# thermometer.net
KiCad netlist of a schematic drawn in EAGLE
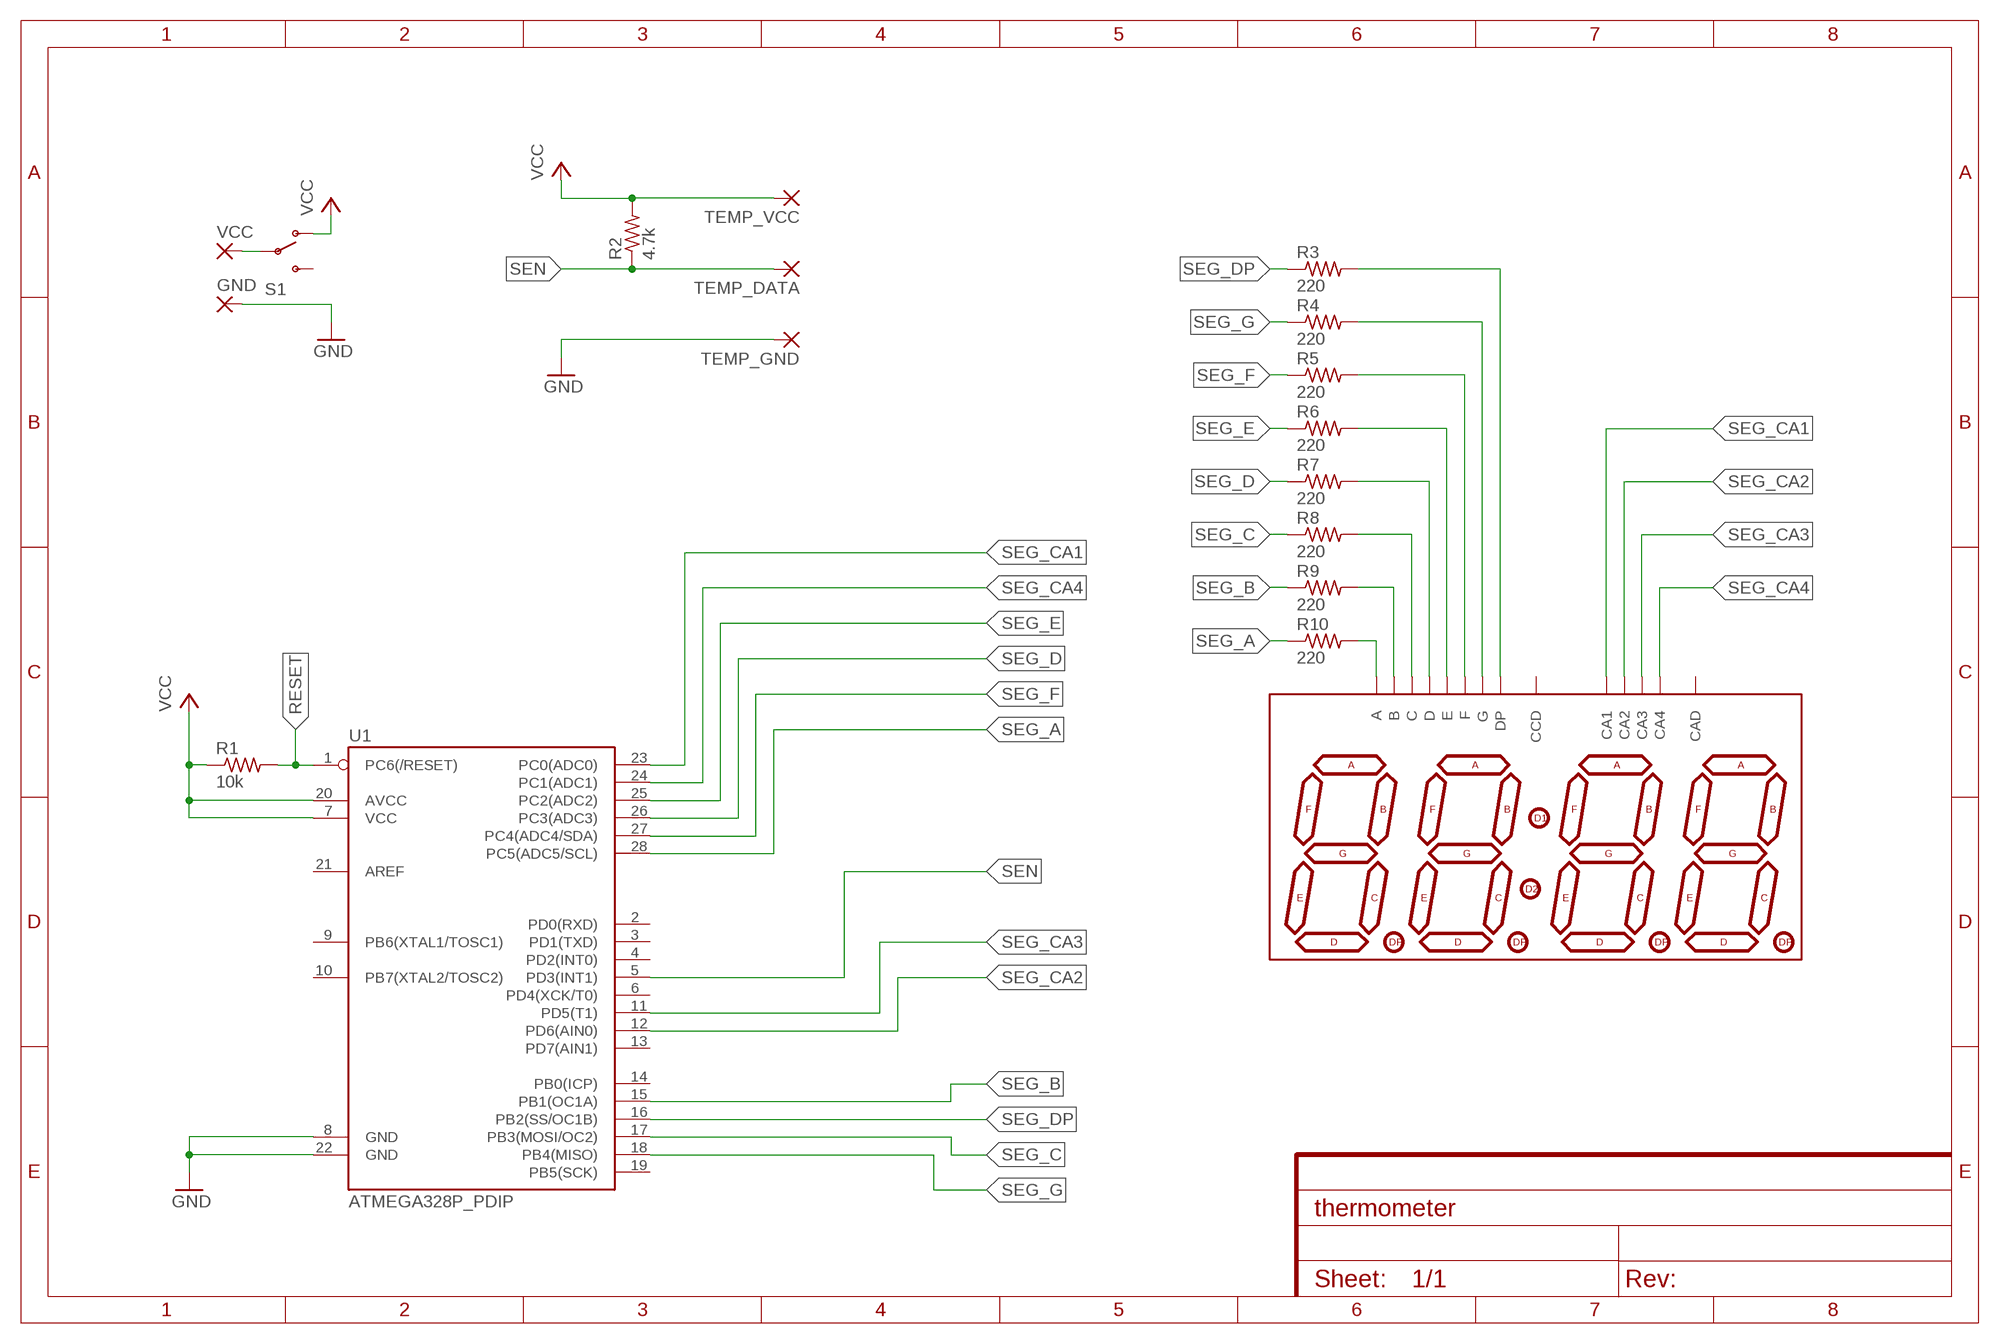
[diagram p0: schematic, sheet 1]

(export (version "E")
  (design (tool "Eeschema 10.0.6"))
  (components
    (comp (ref "GND")
      (value "2,54/0,8")
      (footprint "eagle-import:2,54_0,8")
      (libsource (lib "eagle-import") (part "2,54/0,8"))
    )
    (comp (ref "R1")
      (value "10k")
      (footprint "eagle-import:R0805")
      (libsource (lib "eagle-import") (part "R-US_R0805"))
    )
    (comp (ref "R2")
      (value "4.7k")
      (footprint "eagle-import:R0805")
      (libsource (lib "eagle-import") (part "R-US_R0805"))
    )
    (comp (ref "R3")
      (value "220")
      (footprint "eagle-import:R0805")
      (libsource (lib "eagle-import") (part "R-US_R0805"))
    )
    (comp (ref "R4")
      (value "220")
      (footprint "eagle-import:R0805")
      (libsource (lib "eagle-import") (part "R-US_R0805"))
    )
    (comp (ref "R5")
      (value "220")
      (footprint "eagle-import:R0805")
      (libsource (lib "eagle-import") (part "R-US_R0805"))
    )
    (comp (ref "R6")
      (value "220")
      (footprint "eagle-import:R0805")
      (libsource (lib "eagle-import") (part "R-US_R0805"))
    )
    (comp (ref "R7")
      (value "220")
      (footprint "eagle-import:R0805")
      (libsource (lib "eagle-import") (part "R-US_R0805"))
    )
    (comp (ref "R8")
      (value "220")
      (footprint "eagle-import:R0805")
      (libsource (lib "eagle-import") (part "R-US_R0805"))
    )
    (comp (ref "R9")
      (value "220")
      (footprint "eagle-import:R0805")
      (libsource (lib "eagle-import") (part "R-US_R0805"))
    )
    (comp (ref "R10")
      (value "220")
      (footprint "eagle-import:R0805")
      (libsource (lib "eagle-import") (part "R-US_R0805"))
    )
    (comp (ref "S1")
      (value "SWITCH-SPDTPTH")
      (footprint "eagle-import:SWITCH-SPDT")
      (libsource (lib "eagle-import") (part "SWITCH-SPDTPTH"))
    )
    (comp (ref "TEMP_DATA")
      (value "2,54/0,8")
      (footprint "eagle-import:2,54_0,8")
      (libsource (lib "eagle-import") (part "2,54/0,8"))
    )
    (comp (ref "TEMP_GND")
      (value "2,54/0,8")
      (footprint "eagle-import:2,54_0,8")
      (libsource (lib "eagle-import") (part "2,54/0,8"))
    )
    (comp (ref "TEMP_VCC")
      (value "2,54/0,8")
      (footprint "eagle-import:2,54_0,8")
      (libsource (lib "eagle-import") (part "2,54/0,8"))
    )
    (comp (ref "U1")
      (value "ATMEGA328P_PDIP")
      (footprint "eagle-import:DIL28-3")
      (libsource (lib "eagle-import") (part "ATMEGA328P_PDIP"))
    )
    (comp (ref "U2")
      (value "5461BSDIP14")
      (footprint "eagle-import:5461BS")
      (libsource (lib "eagle-import") (part "5461BSDIP14"))
    )
    (comp (ref "VCC")
      (value "2,54/0,8")
      (footprint "eagle-import:2,54_0,8")
      (libsource (lib "eagle-import") (part "2,54/0,8"))
    )
  )
  (nets
    (net (code "1") (name "GND") (class "Default")
      (node (ref "GND") (pin "1") (pinfunction "P_1") (pintype "passive"))
      (node (ref "TEMP_GND") (pin "1") (pinfunction "P_1") (pintype "passive"))
      (node (ref "U1") (pin "22") (pinfunction "GND_22") (pintype "bidirectional"))
      (node (ref "U1") (pin "8") (pinfunction "GND_8") (pintype "bidirectional"))
    )
    (net (code "2") (name "Net-(R3-Pad2)") (class "Default")
      (node (ref "R3") (pin "2") (pinfunction "2_2") (pintype "passive"))
      (node (ref "U2") (pin "DP") (pinfunction "DP_DP") (pintype "bidirectional"))
    )
    (net (code "3") (name "Net-(R4-Pad2)") (class "Default")
      (node (ref "R4") (pin "2") (pinfunction "2_2") (pintype "passive"))
      (node (ref "U2") (pin "G") (pinfunction "G_G") (pintype "bidirectional"))
    )
    (net (code "4") (name "Net-(R5-Pad2)") (class "Default")
      (node (ref "R5") (pin "2") (pinfunction "2_2") (pintype "passive"))
      (node (ref "U2") (pin "F") (pinfunction "F_F") (pintype "bidirectional"))
    )
    (net (code "5") (name "Net-(R6-Pad2)") (class "Default")
      (node (ref "R6") (pin "2") (pinfunction "2_2") (pintype "passive"))
      (node (ref "U2") (pin "E") (pinfunction "E_E") (pintype "bidirectional"))
    )
    (net (code "6") (name "Net-(R7-Pad2)") (class "Default")
      (node (ref "R7") (pin "2") (pinfunction "2_2") (pintype "passive"))
      (node (ref "U2") (pin "D") (pinfunction "D_D") (pintype "bidirectional"))
    )
    (net (code "7") (name "Net-(R8-Pad2)") (class "Default")
      (node (ref "R8") (pin "2") (pinfunction "2_2") (pintype "passive"))
      (node (ref "U2") (pin "C") (pinfunction "C_C") (pintype "bidirectional"))
    )
    (net (code "8") (name "Net-(R9-Pad2)") (class "Default")
      (node (ref "R9") (pin "2") (pinfunction "2_2") (pintype "passive"))
      (node (ref "U2") (pin "B") (pinfunction "B_B") (pintype "bidirectional"))
    )
    (net (code "9") (name "Net-(R10-Pad2)") (class "Default")
      (node (ref "R10") (pin "2") (pinfunction "2_2") (pintype "passive"))
      (node (ref "U2") (pin "A") (pinfunction "A_A") (pintype "bidirectional"))
    )
    (net (code "10") (name "Net-(S1-P)") (class "Default")
      (node (ref "S1") (pin "2") (pinfunction "P_2") (pintype "passive"))
      (node (ref "VCC") (pin "1") (pinfunction "P_1") (pintype "passive"))
    )
    (net (code "11") (name "RESET") (class "Default")
      (node (ref "R1") (pin "2") (pinfunction "2_2") (pintype "passive"))
      (node (ref "U1") (pin "1") (pinfunction "PC6(/RESET)_1") (pintype "bidirectional"))
    )
    (net (code "12") (name "SEG_A") (class "Default")
      (node (ref "R10") (pin "1") (pinfunction "1_1") (pintype "passive"))
      (node (ref "U1") (pin "28") (pinfunction "PC5(ADC5/SCL)_28") (pintype "bidirectional"))
    )
    (net (code "13") (name "SEG_B") (class "Default")
      (node (ref "R9") (pin "1") (pinfunction "1_1") (pintype "passive"))
      (node (ref "U1") (pin "15") (pinfunction "PB1(OC1A)_15") (pintype "bidirectional"))
    )
    (net (code "14") (name "SEG_C") (class "Default")
      (node (ref "R8") (pin "1") (pinfunction "1_1") (pintype "passive"))
      (node (ref "U1") (pin "17") (pinfunction "PB3(MOSI/OC2)_17") (pintype "bidirectional"))
    )
    (net (code "15") (name "SEG_CA1") (class "Default")
      (node (ref "U1") (pin "23") (pinfunction "PC0(ADC0)_23") (pintype "bidirectional"))
      (node (ref "U2") (pin "CA1") (pinfunction "CA1_CA1") (pintype "bidirectional"))
    )
    (net (code "16") (name "SEG_CA2") (class "Default")
      (node (ref "U1") (pin "12") (pinfunction "PD6(AIN0)_12") (pintype "bidirectional"))
      (node (ref "U2") (pin "CA2") (pinfunction "CA2_CA2") (pintype "bidirectional"))
    )
    (net (code "17") (name "SEG_CA3") (class "Default")
      (node (ref "U1") (pin "11") (pinfunction "PD5(T1)_11") (pintype "bidirectional"))
      (node (ref "U2") (pin "CA3") (pinfunction "CA3_CA3") (pintype "bidirectional"))
    )
    (net (code "18") (name "SEG_CA4") (class "Default")
      (node (ref "U1") (pin "24") (pinfunction "PC1(ADC1)_24") (pintype "bidirectional"))
      (node (ref "U2") (pin "CA4") (pinfunction "CA4_CA4") (pintype "bidirectional"))
    )
    (net (code "19") (name "SEG_D") (class "Default")
      (node (ref "R7") (pin "1") (pinfunction "1_1") (pintype "passive"))
      (node (ref "U1") (pin "26") (pinfunction "PC3(ADC3)_26") (pintype "bidirectional"))
    )
    (net (code "20") (name "SEG_DP") (class "Default")
      (node (ref "R3") (pin "1") (pinfunction "1_1") (pintype "passive"))
      (node (ref "U1") (pin "16") (pinfunction "PB2(SS/OC1B)_16") (pintype "bidirectional"))
    )
    (net (code "21") (name "SEG_E") (class "Default")
      (node (ref "R6") (pin "1") (pinfunction "1_1") (pintype "passive"))
      (node (ref "U1") (pin "25") (pinfunction "PC2(ADC2)_25") (pintype "bidirectional"))
    )
    (net (code "22") (name "SEG_F") (class "Default")
      (node (ref "R5") (pin "1") (pinfunction "1_1") (pintype "passive"))
      (node (ref "U1") (pin "27") (pinfunction "PC4(ADC4/SDA)_27") (pintype "bidirectional"))
    )
    (net (code "23") (name "SEG_G") (class "Default")
      (node (ref "R4") (pin "1") (pinfunction "1_1") (pintype "passive"))
      (node (ref "U1") (pin "18") (pinfunction "PB4(MISO)_18") (pintype "bidirectional"))
    )
    (net (code "24") (name "SEN") (class "Default")
      (node (ref "R2") (pin "1") (pinfunction "1_1") (pintype "passive"))
      (node (ref "TEMP_DATA") (pin "1") (pinfunction "P_1") (pintype "passive"))
      (node (ref "U1") (pin "5") (pinfunction "PD3(INT1)_5") (pintype "bidirectional"))
    )
    (net (code "25") (name "VCC") (class "Default")
      (node (ref "R1") (pin "1") (pinfunction "1_1") (pintype "passive"))
      (node (ref "R2") (pin "2") (pinfunction "2_2") (pintype "passive"))
      (node (ref "S1") (pin "1") (pinfunction "O_1") (pintype "passive"))
      (node (ref "TEMP_VCC") (pin "1") (pinfunction "P_1") (pintype "passive"))
      (node (ref "U1") (pin "20") (pinfunction "AVCC_20") (pintype "bidirectional"))
      (node (ref "U1") (pin "7") (pinfunction "VCC_7") (pintype "bidirectional"))
    )
    (net (code "26") (name "unconnected-(S1-S-Pad3)") (class "Default")
      (node (ref "S1") (pin "3") (pinfunction "S_3") (pintype "passive"))
    )
    (net (code "27") (name "unconnected-(U1-AREF-Pad21)") (class "Default")
      (node (ref "U1") (pin "21") (pinfunction "AREF_21") (pintype "bidirectional"))
    )
    (net (code "28") (name "unconnected-(U1-PB0(ICP)-Pad14)") (class "Default")
      (node (ref "U1") (pin "14") (pinfunction "PB0(ICP)_14") (pintype "bidirectional"))
    )
    (net (code "29") (name "unconnected-(U1-PB5(SCK)-Pad19)") (class "Default")
      (node (ref "U1") (pin "19") (pinfunction "PB5(SCK)_19") (pintype "bidirectional"))
    )
    (net (code "30") (name "unconnected-(U1-PB6(XTAL1{slash}TOSC1)-Pad9)") (class "Default")
      (node (ref "U1") (pin "9") (pinfunction "PB6(XTAL1/TOSC1)_9") (pintype "bidirectional"))
    )
    (net (code "31") (name "unconnected-(U1-PB7(XTAL2{slash}TOSC2)-Pad10)") (class "Default")
      (node (ref "U1") (pin "10") (pinfunction "PB7(XTAL2/TOSC2)_10") (pintype "bidirectional"))
    )
    (net (code "32") (name "unconnected-(U1-PD0(RXD)-Pad2)") (class "Default")
      (node (ref "U1") (pin "2") (pinfunction "PD0(RXD)_2") (pintype "bidirectional"))
    )
    (net (code "33") (name "unconnected-(U1-PD1(TXD)-Pad3)") (class "Default")
      (node (ref "U1") (pin "3") (pinfunction "PD1(TXD)_3") (pintype "bidirectional"))
    )
    (net (code "34") (name "unconnected-(U1-PD2(INT0)-Pad4)") (class "Default")
      (node (ref "U1") (pin "4") (pinfunction "PD2(INT0)_4") (pintype "bidirectional"))
    )
    (net (code "35") (name "unconnected-(U1-PD4(XCK{slash}T0)-Pad6)") (class "Default")
      (node (ref "U1") (pin "6") (pinfunction "PD4(XCK/T0)_6") (pintype "bidirectional"))
    )
    (net (code "36") (name "unconnected-(U1-PD7(AIN1)-Pad13)") (class "Default")
      (node (ref "U1") (pin "13") (pinfunction "PD7(AIN1)_13") (pintype "bidirectional"))
    )
    (net (code "37") (name "unconnected-(U2-PadCAD)") (class "Default")
      (node (ref "U2") (pin "CAD") (pinfunction "CAD_CAD") (pintype "bidirectional"))
    )
    (net (code "38") (name "unconnected-(U2-PadCCD)") (class "Default")
      (node (ref "U2") (pin "CCD") (pinfunction "CCD_CCD") (pintype "bidirectional"))
    )
  )
)
